# beaconboard2.net
KiCad netlist of a schematic drawn in EAGLE
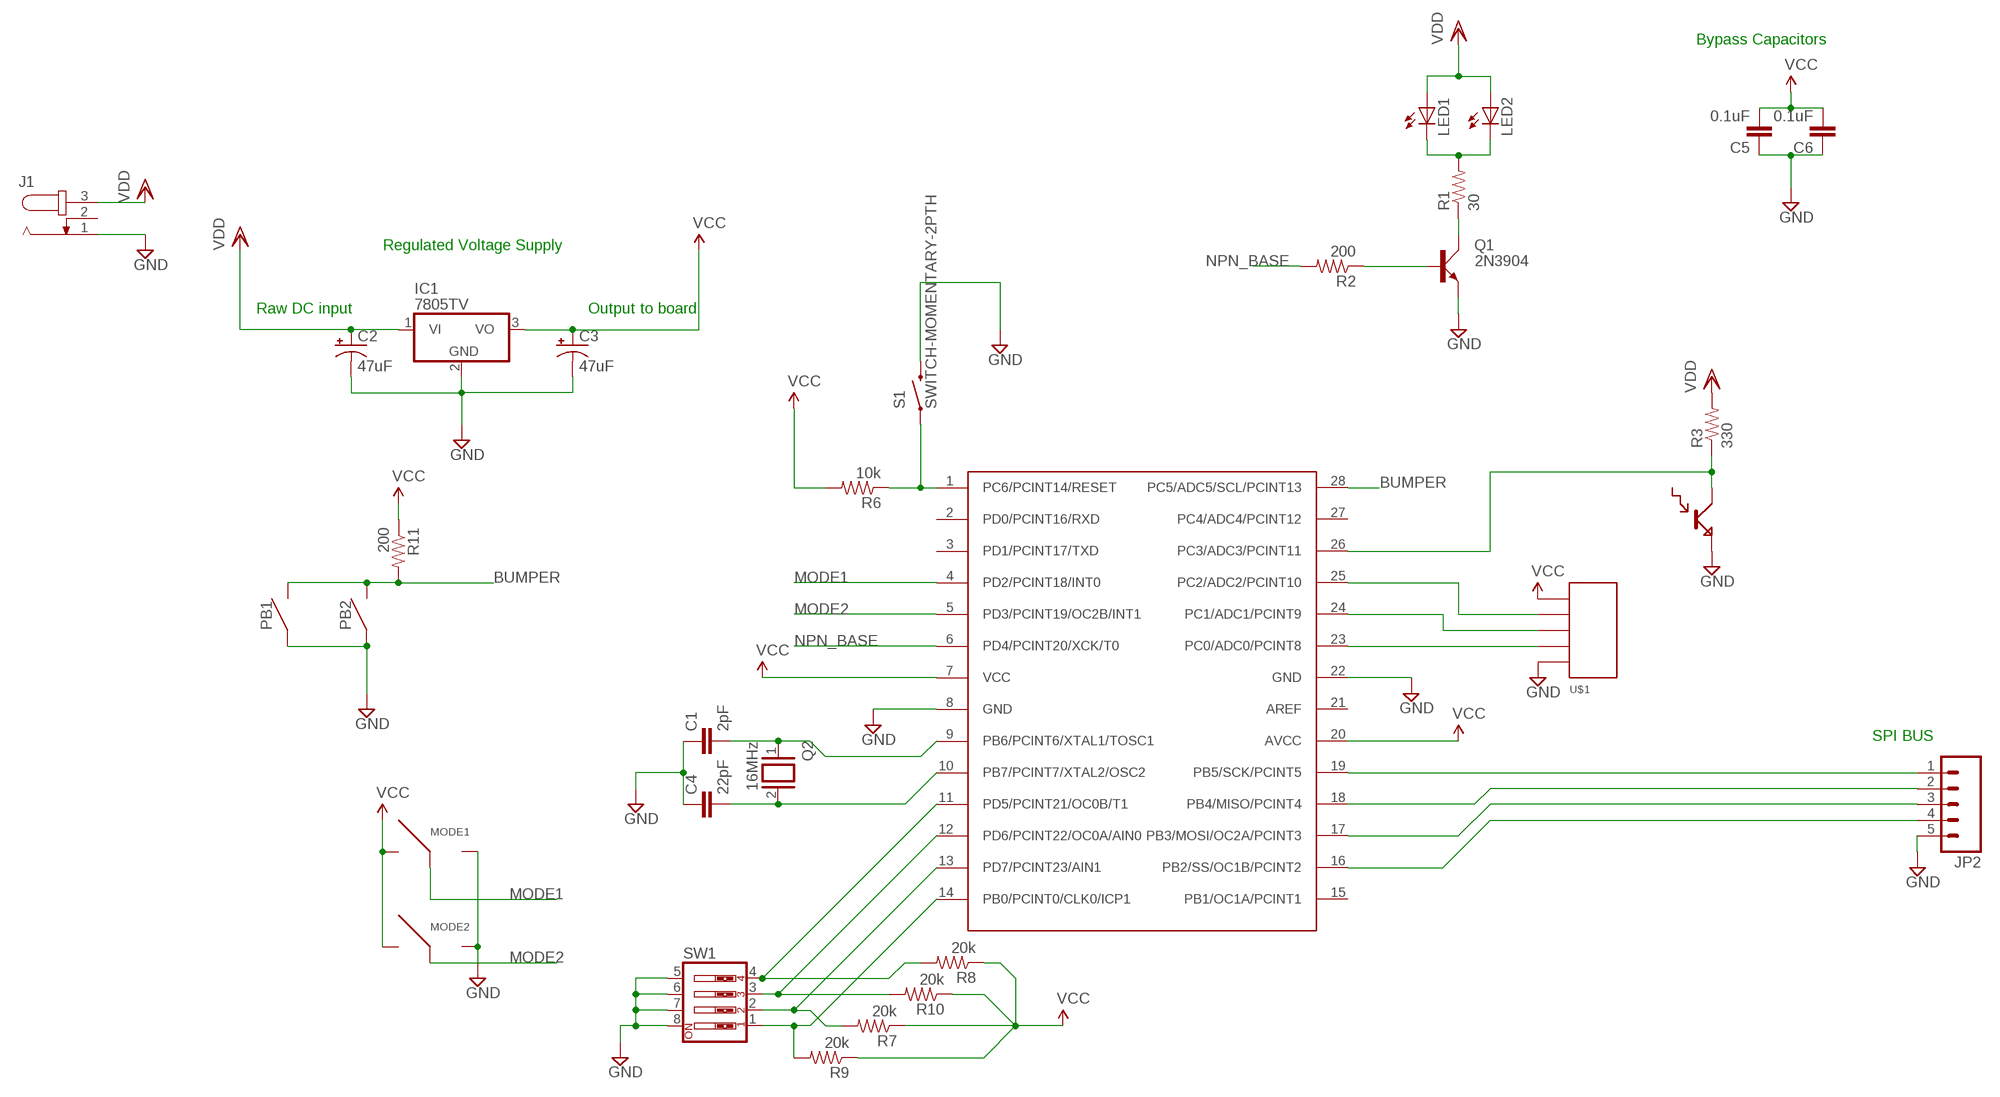
[diagram p0: schematic, sheet 1]

(export (version "E")
  (design (tool "Eeschema 10.0.6"))
  (components
    (comp (ref "C1")
      (value "2pF")
      (footprint "eagle-import:CAP-PTH-SMALL")
      (libsource (lib "eagle-import") (part "CAPPTH"))
    )
    (comp (ref "C2")
      (value "47uF")
      (footprint "eagle-import:CPOL-RADIAL-10UF-25V")
      (libsource (lib "eagle-import") (part "CAP_POLPTH2"))
    )
    (comp (ref "C3")
      (value "47uF")
      (footprint "eagle-import:CPOL-RADIAL-10UF-25V")
      (libsource (lib "eagle-import") (part "CAP_POLPTH2"))
    )
    (comp (ref "C4")
      (value "22pF")
      (footprint "eagle-import:CAP-PTH-SMALL")
      (libsource (lib "eagle-import") (part "CAPPTH"))
    )
    (comp (ref "C5")
      (value "0.1uF")
      (footprint "eagle-import:CAP-PTH-5MM")
      (libsource (lib "eagle-import") (part "CAPPTH1"))
    )
    (comp (ref "C6")
      (value "0.1uF")
      (footprint "eagle-import:CAP-PTH-5MM")
      (libsource (lib "eagle-import") (part "CAPPTH1"))
    )
    (comp (ref "IC1")
      (value "7805TV")
      (footprint "eagle-import:TO220V")
      (libsource (lib "eagle-import") (part "78TV05"))
    )
    (comp (ref "J1")
      (value "JACK-PLUG1")
      (footprint "eagle-import:SPC4078")
      (libsource (lib "eagle-import") (part "JACK-PLUG1"))
    )
    (comp (ref "JP2")
      (value "M05LOCK_LONGPADS")
      (footprint "eagle-import:1X05_LOCK_LONGPADS")
      (libsource (lib "eagle-import") (part "M05LOCK_LONGPADS"))
    )
    (comp (ref "LED1")
      (value "LED-2AC-CP41B-WES")
      (footprint "eagle-import:CP41B")
      (libsource (lib "eagle-import") (part "LED-2AC-CP41B-WES"))
    )
    (comp (ref "LED2")
      (value "LED-2AC-CP41B-WES")
      (footprint "eagle-import:CP41B")
      (libsource (lib "eagle-import") (part "LED-2AC-CP41B-WES"))
    )
    (comp (ref "MODE1")
      (value "SPD_SLIDE_SWITCH")
      (footprint "eagle-import:SPDT_SLIDE_SWITCH")
      (libsource (lib "eagle-import") (part "SPD_SLIDE_SWITCH"))
    )
    (comp (ref "MODE2")
      (value "SPD_SLIDE_SWITCH")
      (footprint "eagle-import:SPDT_SLIDE_SWITCH")
      (libsource (lib "eagle-import") (part "SPD_SLIDE_SWITCH"))
    )
    (comp (ref "PB1")
      (value "D6_PUSHBUTTON")
      (footprint "eagle-import:D6_PUSH_BUTTON")
      (libsource (lib "eagle-import") (part "D6_PUSHBUTTON"))
    )
    (comp (ref "PB2")
      (value "D6_PUSHBUTTON")
      (footprint "eagle-import:D6_PUSH_BUTTON")
      (libsource (lib "eagle-import") (part "D6_PUSHBUTTON"))
    )
    (comp (ref "Q1")
      (value "2N3904")
      (footprint "eagle-import:TO92D")
      (libsource (lib "eagle-import") (part "2N3904"))
    )
    (comp (ref "Q2")
      (value "16MHz")
      (footprint "eagle-import:QS")
      (libsource (lib "eagle-import") (part "XTAL/S"))
    )
    (comp (ref "R1")
      (value "30")
      (footprint "eagle-import:AXIAL-0.4")
      (libsource (lib "eagle-import") (part "RESISTORPTH-1/4W"))
    )
    (comp (ref "R2")
      (value "200")
      (footprint "eagle-import:AXIAL-0.4")
      (libsource (lib "eagle-import") (part "RESISTORPTH-1/4W"))
    )
    (comp (ref "R3")
      (value "330")
      (footprint "eagle-import:AXIAL-0.4")
      (libsource (lib "eagle-import") (part "RESISTORPTH-1/4W"))
    )
    (comp (ref "R6")
      (value "10k")
      (footprint "eagle-import:AXIAL-0.4")
      (libsource (lib "eagle-import") (part "RESISTORPTH-1/4W"))
    )
    (comp (ref "R7")
      (value "20k")
      (footprint "eagle-import:AXIAL-0.4")
      (libsource (lib "eagle-import") (part "RESISTORPTH-1/4W"))
    )
    (comp (ref "R8")
      (value "20k")
      (footprint "eagle-import:AXIAL-0.4")
      (libsource (lib "eagle-import") (part "RESISTORPTH-1/4W"))
    )
    (comp (ref "R9")
      (value "20k")
      (footprint "eagle-import:AXIAL-0.4")
      (libsource (lib "eagle-import") (part "RESISTORPTH-1/4W"))
    )
    (comp (ref "R10")
      (value "20k")
      (footprint "eagle-import:AXIAL-0.4")
      (libsource (lib "eagle-import") (part "RESISTORPTH-1/4W"))
    )
    (comp (ref "R11")
      (value "200")
      (footprint "eagle-import:AXIAL-0.4")
      (libsource (lib "eagle-import") (part "RESISTORPTH-1/4W"))
    )
    (comp (ref "S1")
      (value "SWITCH-MOMENTARY-2PTH")
      (footprint "eagle-import:TACTILE-PTH")
      (libsource (lib "eagle-import") (part "SWITCH-MOMENTARY-2PTH"))
    )
    (comp (ref "SW1")
      (value "SW_DIP-4")
      (footprint "eagle-import:EDG-04")
      (libsource (lib "eagle-import") (part "SW_DIP-4"))
    )
    (comp (ref "U$1")
      (value "1X5_3.5MM_TERMINAL_BLOCK")
      (footprint "eagle-import:1X5_3.5MM_TERMINAL_BLOCK")
      (libsource (lib "eagle-import") (part "1X5_3.5MM_TERMINAL_BLOCK"))
    )
    (comp (ref "U$2")
      (value "BPW77NA")
      (footprint "eagle-import:TO-18")
      (libsource (lib "eagle-import") (part "BPW77NA"))
    )
    (comp (ref "U$4")
      (value "ATMEGA328")
      (footprint "eagle-import:DIL28-3")
      (libsource (lib "eagle-import") (part "ATMEGA328"))
    )
  )
  (nets
    (net (code "1") (name "/BUMPER") (class "Default")
      (node (ref "PB1") (pin "3") (pinfunction "2_3") (pintype "bidirectional"))
      (node (ref "PB1") (pin "4") (pinfunction "2_4") (pintype "bidirectional"))
      (node (ref "PB2") (pin "3") (pinfunction "2_3") (pintype "bidirectional"))
      (node (ref "PB2") (pin "4") (pinfunction "2_4") (pintype "bidirectional"))
      (node (ref "R11") (pin "P$2") (pinfunction "2_P$2") (pintype "passive"))
      (node (ref "U$4") (pin "28") (pinfunction "PC5/ADC5/SCL/PCINT13_28") (pintype "bidirectional"))
    )
    (net (code "2") (name "/MODE1") (class "Default")
      (node (ref "MODE1") (pin "2") (pinfunction "2_2") (pintype "bidirectional"))
      (node (ref "U$4") (pin "4") (pinfunction "PD2/PCINT18/INT0_4") (pintype "bidirectional"))
    )
    (net (code "3") (name "/MODE2") (class "Default")
      (node (ref "MODE2") (pin "2") (pinfunction "2_2") (pintype "bidirectional"))
      (node (ref "U$4") (pin "5") (pinfunction "PD3/PCINT19/OC2B/INT1_5") (pintype "bidirectional"))
    )
    (net (code "4") (name "/NPN_BASE") (class "Default")
      (node (ref "R2") (pin "P$2") (pinfunction "2_P$2") (pintype "passive"))
      (node (ref "U$4") (pin "6") (pinfunction "PD4/PCINT20/XCK/T0_6") (pintype "bidirectional"))
    )
    (net (code "5") (name "GND") (class "Default")
      (node (ref "C1") (pin "1") (pinfunction "1_1") (pintype "passive"))
      (node (ref "C2") (pin "2") (pinfunction "-_2") (pintype "passive"))
      (node (ref "C3") (pin "2") (pinfunction "-_2") (pintype "passive"))
      (node (ref "C4") (pin "1") (pinfunction "1_1") (pintype "passive"))
      (node (ref "C5") (pin "1") (pinfunction "1_1") (pintype "passive"))
      (node (ref "C6") (pin "1") (pinfunction "1_1") (pintype "passive"))
      (node (ref "IC1") (pin "2") (pinfunction "GND_2") (pintype "passive"))
      (node (ref "J1") (pin "1") (pinfunction "1_1") (pintype "passive"))
      (node (ref "JP2") (pin "5") (pinfunction "5_5") (pintype "passive"))
      (node (ref "MODE1") (pin "3") (pinfunction "3_3") (pintype "bidirectional"))
      (node (ref "MODE2") (pin "3") (pinfunction "3_3") (pintype "bidirectional"))
      (node (ref "PB1") (pin "1") (pinfunction "1_1") (pintype "bidirectional"))
      (node (ref "PB1") (pin "2") (pinfunction "1_2") (pintype "bidirectional"))
      (node (ref "PB2") (pin "1") (pinfunction "1_1") (pintype "bidirectional"))
      (node (ref "PB2") (pin "2") (pinfunction "1_2") (pintype "bidirectional"))
      (node (ref "Q1") (pin "E") (pinfunction "E_E") (pintype "passive"))
      (node (ref "S1") (pin "3") (pinfunction "2_3") (pintype "passive"))
      (node (ref "SW1") (pin "5") (pinfunction "5_5") (pintype "passive"))
      (node (ref "SW1") (pin "6") (pinfunction "6_6") (pintype "passive"))
      (node (ref "SW1") (pin "7") (pinfunction "7_7") (pintype "passive"))
      (node (ref "SW1") (pin "8") (pinfunction "8_8") (pintype "passive"))
      (node (ref "U$1") (pin "5") (pinfunction "5_5") (pintype "bidirectional"))
      (node (ref "U$2") (pin "E") (pinfunction "E_E") (pintype "bidirectional"))
      (node (ref "U$4") (pin "22") (pinfunction "GND_22") (pintype "power_in"))
      (node (ref "U$4") (pin "8") (pinfunction "GND_8") (pintype "power_in"))
    )
    (net (code "6") (name "Net-(R1-1)") (class "Default")
      (node (ref "Q1") (pin "C") (pinfunction "C_C") (pintype "passive"))
      (node (ref "R1") (pin "P$1") (pinfunction "1_P$1") (pintype "passive"))
    )
    (net (code "7") (name "Net-(R1-2)") (class "Default")
      (node (ref "LED1") (pin "1") (pinfunction "C_1") (pintype "passive"))
      (node (ref "LED1") (pin "4") (pinfunction "C_4") (pintype "passive"))
      (node (ref "LED2") (pin "1") (pinfunction "C_1") (pintype "passive"))
      (node (ref "LED2") (pin "4") (pinfunction "C_4") (pintype "passive"))
      (node (ref "R1") (pin "P$2") (pinfunction "2_P$2") (pintype "passive"))
    )
    (net (code "8") (name "Net-(R2-1)") (class "Default")
      (node (ref "Q1") (pin "B") (pinfunction "B_B") (pintype "passive"))
      (node (ref "R2") (pin "P$1") (pinfunction "1_P$1") (pintype "passive"))
    )
    (net (code "9") (name "Net-(R3-1)") (class "Default")
      (node (ref "R3") (pin "P$1") (pinfunction "1_P$1") (pintype "passive"))
      (node (ref "U$2") (pin "C") (pinfunction "C_C") (pintype "bidirectional"))
      (node (ref "U$4") (pin "26") (pinfunction "PC3/ADC3/PCINT11_26") (pintype "bidirectional"))
    )
    (net (code "10") (name "Net-(R6-1)") (class "Default")
      (node (ref "R6") (pin "P$1") (pinfunction "1_P$1") (pintype "passive"))
      (node (ref "S1") (pin "1") (pinfunction "1_1") (pintype "passive"))
      (node (ref "U$4") (pin "1") (pinfunction "PC6/PCINT14/RESET_1") (pintype "bidirectional"))
    )
    (net (code "11") (name "Net-(R7-2)") (class "Default")
      (node (ref "R7") (pin "P$2") (pinfunction "2_P$2") (pintype "passive"))
      (node (ref "SW1") (pin "2") (pinfunction "2_2") (pintype "passive"))
      (node (ref "U$4") (pin "13") (pinfunction "PD7/PCINT23/AIN1_13") (pintype "bidirectional"))
    )
    (net (code "12") (name "Net-(R8-2)") (class "Default")
      (node (ref "R8") (pin "P$2") (pinfunction "2_P$2") (pintype "passive"))
      (node (ref "SW1") (pin "4") (pinfunction "4_4") (pintype "passive"))
      (node (ref "U$4") (pin "11") (pinfunction "PD5/PCINT21/OC0B/T1_11") (pintype "bidirectional"))
    )
    (net (code "13") (name "Net-(R9-2)") (class "Default")
      (node (ref "R9") (pin "P$2") (pinfunction "2_P$2") (pintype "passive"))
      (node (ref "SW1") (pin "1") (pinfunction "1_1") (pintype "passive"))
      (node (ref "U$4") (pin "14") (pinfunction "PB0/PCINT0/CLK0/ICP1_14") (pintype "bidirectional"))
    )
    (net (code "14") (name "Net-(R10-2)") (class "Default")
      (node (ref "R10") (pin "P$2") (pinfunction "2_P$2") (pintype "passive"))
      (node (ref "SW1") (pin "3") (pinfunction "3_3") (pintype "passive"))
      (node (ref "U$4") (pin "12") (pinfunction "PD6/PCINT22/OC0A/AIN0_12") (pintype "bidirectional"))
    )
    (net (code "15") (name "Net-(U$4-PB2{slash}SS{slash}OC1B{slash}PCINT2)") (class "Default")
      (node (ref "JP2") (pin "4") (pinfunction "4_4") (pintype "passive"))
      (node (ref "U$4") (pin "16") (pinfunction "PB2/SS/OC1B/PCINT2_16") (pintype "bidirectional"))
    )
    (net (code "16") (name "Net-(U$4-PB3{slash}MOSI{slash}OC2A{slash}PCINT3)") (class "Default")
      (node (ref "JP2") (pin "3") (pinfunction "3_3") (pintype "passive"))
      (node (ref "U$4") (pin "17") (pinfunction "PB3/MOSI/OC2A/PCINT3_17") (pintype "bidirectional"))
    )
    (net (code "17") (name "Net-(U$4-PB4{slash}MISO{slash}PCINT4)") (class "Default")
      (node (ref "JP2") (pin "2") (pinfunction "2_2") (pintype "passive"))
      (node (ref "U$4") (pin "18") (pinfunction "PB4/MISO/PCINT4_18") (pintype "bidirectional"))
    )
    (net (code "18") (name "Net-(U$4-PB5{slash}SCK{slash}PCINT5)") (class "Default")
      (node (ref "JP2") (pin "1") (pinfunction "1_1") (pintype "passive"))
      (node (ref "U$4") (pin "19") (pinfunction "PB5/SCK/PCINT5_19") (pintype "bidirectional"))
    )
    (net (code "19") (name "Net-(U$4-PB6{slash}PCINT6{slash}XTAL1{slash}TOSC1)") (class "Default")
      (node (ref "C1") (pin "2") (pinfunction "2_2") (pintype "passive"))
      (node (ref "Q2") (pin "1") (pinfunction "1_1") (pintype "passive"))
      (node (ref "U$4") (pin "9") (pinfunction "PB6/PCINT6/XTAL1/TOSC1_9") (pintype "bidirectional"))
    )
    (net (code "20") (name "Net-(U$4-PB7{slash}PCINT7{slash}XTAL2{slash}OSC2)") (class "Default")
      (node (ref "C4") (pin "2") (pinfunction "2_2") (pintype "passive"))
      (node (ref "Q2") (pin "2") (pinfunction "2_2") (pintype "passive"))
      (node (ref "U$4") (pin "10") (pinfunction "PB7/PCINT7/XTAL2/OSC2_10") (pintype "bidirectional"))
    )
    (net (code "21") (name "Net-(U$4-PC0{slash}ADC0{slash}PCINT8)") (class "Default")
      (node (ref "U$1") (pin "4") (pinfunction "4_4") (pintype "bidirectional"))
      (node (ref "U$4") (pin "23") (pinfunction "PC0/ADC0/PCINT8_23") (pintype "bidirectional"))
    )
    (net (code "22") (name "Net-(U$4-PC1{slash}ADC1{slash}PCINT9)") (class "Default")
      (node (ref "U$1") (pin "3") (pinfunction "3_3") (pintype "bidirectional"))
      (node (ref "U$4") (pin "24") (pinfunction "PC1/ADC1/PCINT9_24") (pintype "bidirectional"))
    )
    (net (code "23") (name "Net-(U$4-PC2{slash}ADC2{slash}PCINT10)") (class "Default")
      (node (ref "U$1") (pin "2") (pinfunction "2_2") (pintype "bidirectional"))
      (node (ref "U$4") (pin "25") (pinfunction "PC2/ADC2/PCINT10_25") (pintype "bidirectional"))
    )
    (net (code "24") (name "VCC") (class "Default")
      (node (ref "C3") (pin "1") (pinfunction "+_1") (pintype "passive"))
      (node (ref "C5") (pin "2") (pinfunction "2_2") (pintype "passive"))
      (node (ref "C6") (pin "2") (pinfunction "2_2") (pintype "passive"))
      (node (ref "IC1") (pin "3") (pinfunction "VO_3") (pintype "passive"))
      (node (ref "MODE1") (pin "1") (pinfunction "1_1") (pintype "bidirectional"))
      (node (ref "MODE2") (pin "1") (pinfunction "1_1") (pintype "bidirectional"))
      (node (ref "R10") (pin "P$1") (pinfunction "1_P$1") (pintype "passive"))
      (node (ref "R11") (pin "P$1") (pinfunction "1_P$1") (pintype "passive"))
      (node (ref "R6") (pin "P$2") (pinfunction "2_P$2") (pintype "passive"))
      (node (ref "R7") (pin "P$1") (pinfunction "1_P$1") (pintype "passive"))
      (node (ref "R8") (pin "P$1") (pinfunction "1_P$1") (pintype "passive"))
      (node (ref "R9") (pin "P$1") (pinfunction "1_P$1") (pintype "passive"))
      (node (ref "U$1") (pin "1") (pinfunction "1_1") (pintype "bidirectional"))
      (node (ref "U$4") (pin "20") (pinfunction "AVCC_20") (pintype "bidirectional"))
      (node (ref "U$4") (pin "7") (pinfunction "VCC_7") (pintype "power_in"))
    )
    (net (code "25") (name "VDD") (class "Default")
      (node (ref "C2") (pin "1") (pinfunction "+_1") (pintype "passive"))
      (node (ref "IC1") (pin "1") (pinfunction "VI_1") (pintype "input"))
      (node (ref "J1") (pin "3") (pinfunction "3_3") (pintype "passive"))
      (node (ref "LED1") (pin "2") (pinfunction "A_2") (pintype "passive"))
      (node (ref "LED1") (pin "3") (pinfunction "A_3") (pintype "passive"))
      (node (ref "LED2") (pin "2") (pinfunction "A_2") (pintype "passive"))
      (node (ref "LED2") (pin "3") (pinfunction "A_3") (pintype "passive"))
      (node (ref "R3") (pin "P$2") (pinfunction "2_P$2") (pintype "passive"))
    )
    (net (code "26") (name "unconnected-(J1-Pad2)") (class "Default")
      (node (ref "J1") (pin "2") (pinfunction "2_2") (pintype "passive"))
    )
    (net (code "27") (name "unconnected-(U$4-AREF-Pad21)") (class "Default")
      (node (ref "U$4") (pin "21") (pinfunction "AREF_21") (pintype "bidirectional"))
    )
    (net (code "28") (name "unconnected-(U$4-PB1{slash}OC1A{slash}PCINT1-Pad15)") (class "Default")
      (node (ref "U$4") (pin "15") (pinfunction "PB1/OC1A/PCINT1_15") (pintype "bidirectional"))
    )
    (net (code "29") (name "unconnected-(U$4-PC4{slash}ADC4{slash}PCINT12-Pad27)") (class "Default")
      (node (ref "U$4") (pin "27") (pinfunction "PC4/ADC4/PCINT12_27") (pintype "bidirectional"))
    )
    (net (code "30") (name "unconnected-(U$4-PD0{slash}PCINT16{slash}RXD-Pad2)") (class "Default")
      (node (ref "U$4") (pin "2") (pinfunction "PD0/PCINT16/RXD_2") (pintype "bidirectional"))
    )
    (net (code "31") (name "unconnected-(U$4-PD1{slash}PCINT17{slash}TXD-Pad3)") (class "Default")
      (node (ref "U$4") (pin "3") (pinfunction "PD1/PCINT17/TXD_3") (pintype "bidirectional"))
    )
  )
)
